# RVP_OVP_HC.net
KiCad netlist of a schematic drawn in Altium Designer
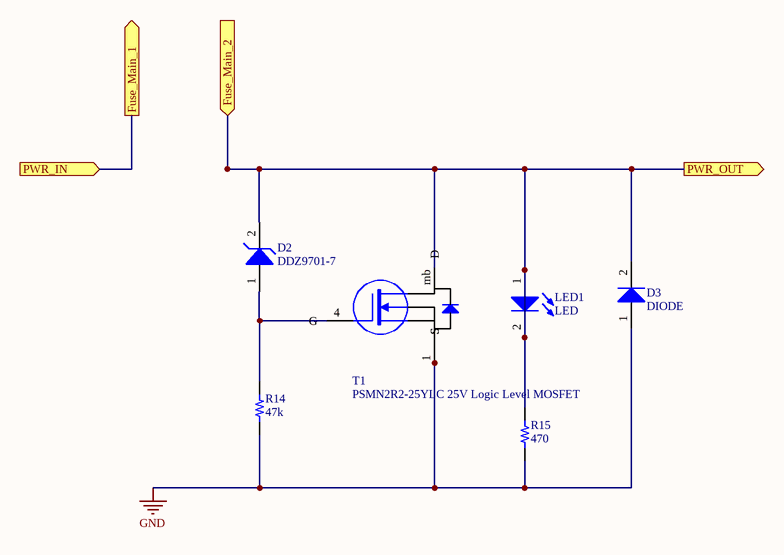
[diagram p0: RVP_OVP_HC.SchDoc]

(export (version "E")
  (design (tool "Eeschema 10.0.6"))
  (components
    (comp (ref "D2")
      (value "DDZ9701-7")
      (footprint "SOD123F")
      (description "Zener Diode 14V 500mW ±5% Surface Mount SOD-123")
      (fields (field (name "POWER") "500mW"))
      (libsource (lib "Altium-Lib") (part "Zener"))
    )
    (comp (ref "D3")
      (value "DIODE")
      (footprint "TO-277")
      (fields (field (name "MFRPARTNO") "FSV20100V"))
      (libsource (lib "Altium-Lib") (part "DIODE"))
    )
    (comp (ref "LED1") (value "LED") (footprint "0805_LED") (libsource (lib "Altium-Lib") (part "LED")))
    (comp (ref "R14")
      (value "47k")
      (footprint "RES 0805/2012")
      (fields
        (field (name "TOLERANCE") "1%")
        (field (name "POWER") "1/10W")
        (field (name "Comment") "Resistor 47k 0805 1/10W 1%")
        (field (name "CREATED_BY") "Nick Mah")
      )
      (libsource (lib "Altium-Lib") (part "Resistor"))
    )
    (comp (ref "R15")
      (value "470")
      (footprint "RES 0805/2012")
      (fields
        (field (name "TOLERANCE") "1%")
        (field (name "POWER") "1/10W")
        (field (name "Comment") "Resistor 470 0805 1/10W 1%")
        (field (name "CREATED_BY") "Nick Mah")
      )
      (libsource (lib "Altium-Lib") (part "Resistor"))
    )
    (comp (ref "T1")
      (value "PSMN2R2-25YLC 25V Logic Level MOSFET")
      (footprint "LFPAK-SO8")
      (description "N-Channel 25V 100A (Tc) 106W (Tc) Surface Mount LFPAK56, Power-SO8")
      (fields (field (name "MFRPARTNO") "PSMN2R2-25YLC,115") (field (name "CREATED_BY") "Nick"))
      (libsource (lib "Altium-Lib") (part "PSMN2R2-25YLC 25V Logic Level MOSFET"))
    )
  )
  (nets
    (net (code "2") (name "/Fuse_Main_2") (class "Default")
      (node (ref "D2") (pin "2") (pinfunction "K_2") (pintype "passive"))
      (node (ref "D3") (pin "2") (pinfunction "K_2") (pintype "passive"))
      (node (ref "LED1") (pin "1") (pinfunction "A_1") (pintype "passive"))
      (node (ref "LED1") (pin "2") (pinfunction "K_2") (pintype "passive"))
      (node (ref "R15") (pin "2") (pinfunction "2_2") (pintype "passive"))
      (node (ref "T1") (pin "mb") (pinfunction "D_mb") (pintype "passive"))
    )
    (net (code "3") (name "GND") (class "Default")
      (node (ref "D3") (pin "1") (pinfunction "A_1") (pintype "passive"))
      (node (ref "R14") (pin "1") (pinfunction "1_1") (pintype "passive"))
      (node (ref "R15") (pin "1") (pinfunction "1_1") (pintype "passive"))
      (node (ref "T1") (pin "1") (pinfunction "S_1") (pintype "passive"))
      (node (ref "T1") (pin "2") (pinfunction "S_2") (pintype "passive"))
      (node (ref "T1") (pin "3") (pinfunction "S_3") (pintype "passive"))
    )
    (net (code "4") (name "Net-(D2-A)") (class "Default")
      (node (ref "D2") (pin "1") (pinfunction "A_1") (pintype "passive"))
      (node (ref "R14") (pin "2") (pinfunction "2_2") (pintype "passive"))
      (node (ref "T1") (pin "4") (pinfunction "G_4") (pintype "passive"))
    )
  )
)
